# tiny_encoder_board.net
KiCad netlist of a schematic drawn in EAGLE
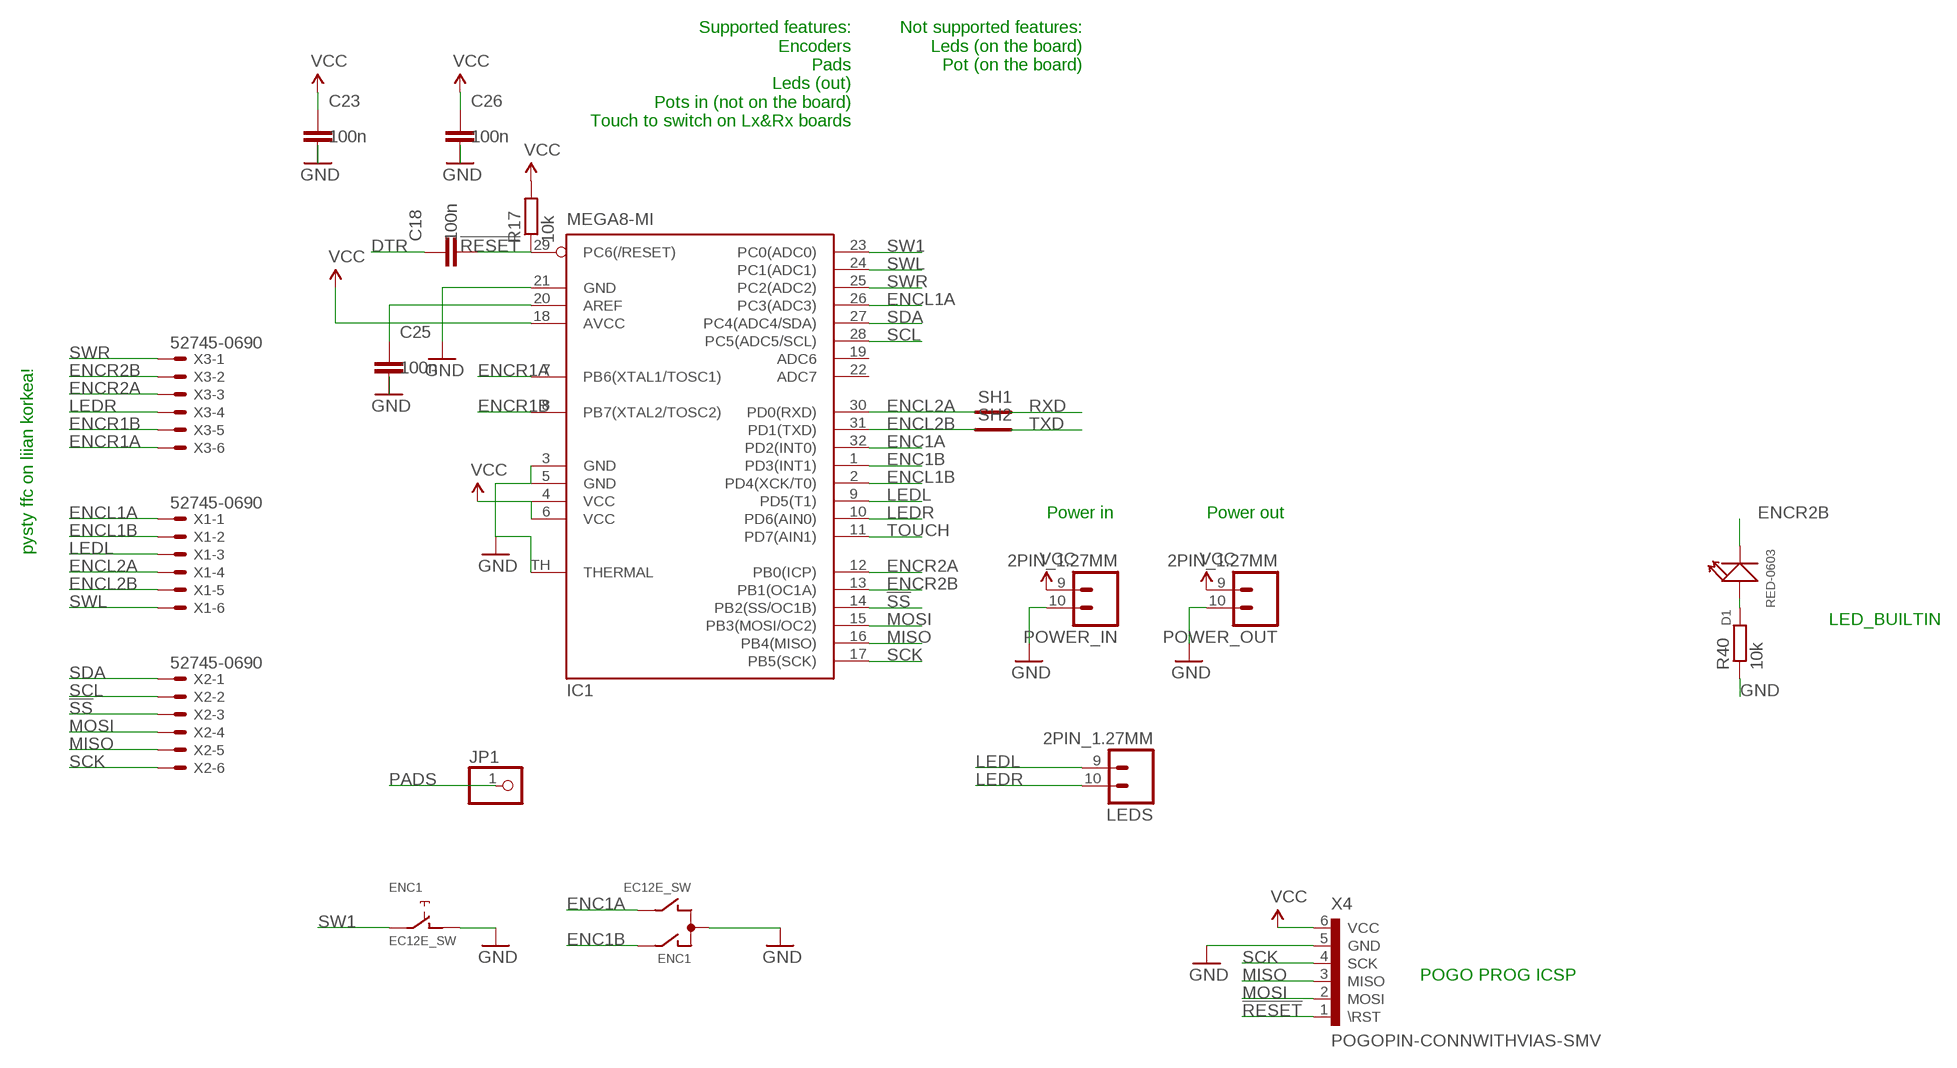
[diagram p0: schematic, sheet 1]
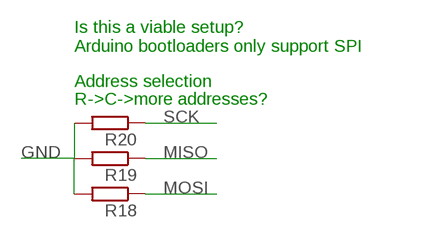
[diagram p1: schematic, sheet 2]
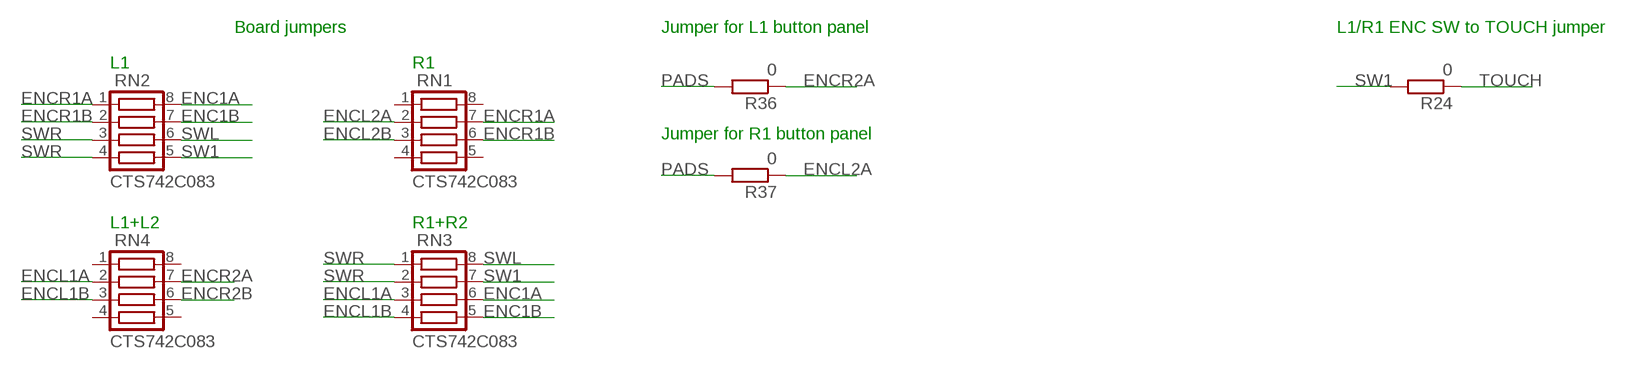
[diagram p2: schematic, sheet 3]

(export (version "E")
  (design (tool "Eeschema 10.0.6"))
  (components
    (comp (ref "C18")
      (value "100n")
      (footprint "eagle-import:C0402")
      (libsource (lib "eagle-import") (part "C-EUC0402"))
    )
    (comp (ref "C23")
      (value "100n")
      (footprint "eagle-import:C0402")
      (libsource (lib "eagle-import") (part "C-EUC0402"))
    )
    (comp (ref "C25")
      (value "100n")
      (footprint "eagle-import:C0402")
      (libsource (lib "eagle-import") (part "C-EUC0402"))
    )
    (comp (ref "C26")
      (value "100n")
      (footprint "eagle-import:C0402")
      (libsource (lib "eagle-import") (part "C-EUC0402"))
    )
    (comp (ref "D1")
      (value "RED-0603")
      (footprint "eagle-import:LED-0603")
      (fields (field (name "MPN") "19-217-R6C-AL1M2VY-3T"))
      (libsource (lib "eagle-import") (part "LED-SMD-RED-DIFFUSED(0603)"))
    )
    (comp (ref "ENC1")
      (value "EC12E_SW")
      (footprint "eagle-import:ALPS_EC12E_SW")
      (fields (field (name "MPN") "EC12E2424407"))
      (libsource (lib "eagle-import") (part "EC12E_SW"))
    )
    (comp (ref "IC1")
      (value "MEGA8-MI")
      (footprint "eagle-import:MLF32-TH")
      (fields (field (name "MPN") "ATMEGA88PA-MU"))
      (libsource (lib "eagle-import") (part "MEGA8-MI"))
    )
    (comp (ref "JP1")
      (value "PINHD-1X1")
      (footprint "eagle-import:1X01")
      (libsource (lib "eagle-import") (part "PINHD-1X1"))
    )
    (comp (ref "LEDS")
      (value "2PIN_1.27MM")
      (footprint "eagle-import:1X02_1.27MM_NO_SILK")
      (libsource (lib "eagle-import") (part "2PIN_1.27MM"))
    )
    (comp (ref "POWER_IN")
      (value "2PIN_1.27MM")
      (footprint "eagle-import:1X02_1.27MM_NO_SILK")
      (libsource (lib "eagle-import") (part "2PIN_1.27MM"))
    )
    (comp (ref "POWER_OUT")
      (value "2PIN_1.27MM")
      (footprint "eagle-import:1X02_1.27MM_NO_SILK")
      (libsource (lib "eagle-import") (part "2PIN_1.27MM"))
    )
    (comp (ref "R17")
      (value "10k")
      (footprint "eagle-import:R0402")
      (libsource (lib "eagle-import") (part "rcl_334_R-EU_R0402"))
    )
    (comp (ref "R40")
      (value "10k")
      (footprint "eagle-import:R0402")
      (libsource (lib "eagle-import") (part "rcl_334_R-EU_R0402"))
    )
    (comp (ref "SH1")
      (value "SHORT")
      (footprint "eagle-import:SHORT_TOP_8MIL")
      (libsource (lib "eagle-import") (part "SHORT"))
    )
    (comp (ref "SH2")
      (value "SHORT")
      (footprint "eagle-import:SHORT_TOP_8MIL")
      (libsource (lib "eagle-import") (part "SHORT"))
    )
    (comp (ref "X1")
      (value "52745-0690")
      (footprint "eagle-import:52745-0690")
      (fields (field (name "MF") "MOLEX"))
      (libsource (lib "eagle-import") (part "52745-0690"))
    )
    (comp (ref "X2")
      (value "52745-0690")
      (footprint "eagle-import:52745-0690")
      (fields (field (name "MF") "MOLEX"))
      (libsource (lib "eagle-import") (part "52745-0690"))
    )
    (comp (ref "X3")
      (value "52745-0690")
      (footprint "eagle-import:52745-0690")
      (fields (field (name "MF") "MOLEX"))
      (libsource (lib "eagle-import") (part "52745-0690"))
    )
    (comp (ref "X4")
      (value "POGOPIN-CONNWITHVIAS-SMV")
      (footprint "eagle-import:POGOPROG-CONN-OH-SMALLERVIAS")
      (libsource (lib "eagle-import") (part "POGOPIN-CONNWITHVIAS-SMV"))
    )
    (comp (ref "R24")
      (value "0")
      (footprint "eagle-import:R0402")
      (fields (field (name "SPICEPREFIX") "R"))
      (libsource (lib "eagle-import") (part "rcl_334_R-EU_R0402"))
    )
    (comp (ref "R36")
      (value "0")
      (footprint "eagle-import:R0603")
      (fields (field (name "SPICEPREFIX") "R"))
      (libsource (lib "eagle-import") (part "R-EU_R0603"))
    )
    (comp (ref "R37")
      (value "0")
      (footprint "eagle-import:R0402")
      (fields (field (name "SPICEPREFIX") "R"))
      (libsource (lib "eagle-import") (part "rcl_334_R-EU_R0402"))
    )
    (comp (ref "RN1")
      (value "CTS742C083")
      (footprint "eagle-import:CTS742C083")
      (libsource (lib "eagle-import") (part "CTS742C083"))
    )
    (comp (ref "RN2")
      (value "CTS742C083")
      (footprint "eagle-import:CTS742C083")
      (libsource (lib "eagle-import") (part "CTS742C083"))
    )
    (comp (ref "RN3")
      (value "CTS742C083")
      (footprint "eagle-import:CTS742C083")
      (libsource (lib "eagle-import") (part "CTS742C083"))
    )
    (comp (ref "RN4")
      (value "CTS742C083")
      (footprint "eagle-import:CTS742C083")
      (libsource (lib "eagle-import") (part "CTS742C083"))
    )
    (comp (ref "R18")
      (value "R-EU_R0402")
      (footprint "eagle-import:R0402")
      (libsource (lib "eagle-import") (part "rcl_334_R-EU_R0402"))
    )
    (comp (ref "R19")
      (value "R-EU_R0402")
      (footprint "eagle-import:R0402")
      (libsource (lib "eagle-import") (part "rcl_334_R-EU_R0402"))
    )
    (comp (ref "R20")
      (value "R-EU_R0402")
      (footprint "eagle-import:R0402")
      (libsource (lib "eagle-import") (part "rcl_334_R-EU_R0402"))
    )
  )
  (nets
    (net (code "1") (name "DTR") (class "Default")
      (node (ref "C18") (pin "1") (pinfunction "1_1") (pintype "passive"))
    )
    (net (code "2") (name "ENC1A") (class "Default")
      (node (ref "ENC1") (pin "B") (pinfunction "B_B") (pintype "passive"))
      (node (ref "IC1") (pin "32") (pinfunction "PD2(INT0)_32") (pintype "bidirectional"))
      (node (ref "RN2") (pin "8") (pinfunction "8_8") (pintype "passive"))
      (node (ref "RN3") (pin "6") (pinfunction "6_6") (pintype "passive"))
    )
    (net (code "3") (name "ENC1B") (class "Default")
      (node (ref "ENC1") (pin "A") (pinfunction "A_A") (pintype "passive"))
      (node (ref "IC1") (pin "1") (pinfunction "PD3(INT1)_1") (pintype "bidirectional"))
      (node (ref "RN2") (pin "7") (pinfunction "7_7") (pintype "passive"))
      (node (ref "RN3") (pin "5") (pinfunction "5_5") (pintype "passive"))
    )
    (net (code "4") (name "ENCL1A") (class "Default")
      (node (ref "IC1") (pin "26") (pinfunction "PC3(ADC3)_26") (pintype "bidirectional"))
      (node (ref "RN3") (pin "3") (pinfunction "3_3") (pintype "passive"))
      (node (ref "RN4") (pin "2") (pinfunction "2_2") (pintype "passive"))
      (node (ref "X1") (pin "1") (pinfunction "S_1") (pintype "passive"))
    )
    (net (code "5") (name "ENCL1B") (class "Default")
      (node (ref "IC1") (pin "2") (pinfunction "PD4(XCK/T0)_2") (pintype "bidirectional"))
      (node (ref "RN3") (pin "4") (pinfunction "4_4") (pintype "passive"))
      (node (ref "RN4") (pin "3") (pinfunction "3_3") (pintype "passive"))
      (node (ref "X1") (pin "2") (pinfunction "S_2") (pintype "passive"))
    )
    (net (code "6") (name "ENCL2A") (class "Default")
      (node (ref "IC1") (pin "30") (pinfunction "PD0(RXD)_30") (pintype "bidirectional"))
      (node (ref "R37") (pin "1") (pinfunction "1_1") (pintype "passive"))
      (node (ref "RN1") (pin "2") (pinfunction "2_2") (pintype "passive"))
      (node (ref "SH1") (pin "P$1") (pinfunction "P$1_P$1") (pintype "bidirectional"))
      (node (ref "X1") (pin "4") (pinfunction "S_4") (pintype "passive"))
    )
    (net (code "7") (name "ENCL2B") (class "Default")
      (node (ref "IC1") (pin "31") (pinfunction "PD1(TXD)_31") (pintype "bidirectional"))
      (node (ref "RN1") (pin "3") (pinfunction "3_3") (pintype "passive"))
      (node (ref "SH2") (pin "P$1") (pinfunction "P$1_P$1") (pintype "bidirectional"))
      (node (ref "X1") (pin "5") (pinfunction "S_5") (pintype "passive"))
    )
    (net (code "8") (name "ENCR1A") (class "Default")
      (node (ref "IC1") (pin "7") (pinfunction "PB6(XTAL1/TOSC1)_7") (pintype "bidirectional"))
      (node (ref "RN1") (pin "7") (pinfunction "7_7") (pintype "passive"))
      (node (ref "RN2") (pin "1") (pinfunction "1_1") (pintype "passive"))
      (node (ref "X3") (pin "6") (pinfunction "S_6") (pintype "passive"))
    )
    (net (code "9") (name "ENCR1B") (class "Default")
      (node (ref "IC1") (pin "8") (pinfunction "PB7(XTAL2/TOSC2)_8") (pintype "bidirectional"))
      (node (ref "RN1") (pin "6") (pinfunction "6_6") (pintype "passive"))
      (node (ref "RN2") (pin "2") (pinfunction "2_2") (pintype "passive"))
      (node (ref "X3") (pin "5") (pinfunction "S_5") (pintype "passive"))
    )
    (net (code "10") (name "ENCR2A") (class "Default")
      (node (ref "IC1") (pin "12") (pinfunction "PB0(ICP)_12") (pintype "bidirectional"))
      (node (ref "R36") (pin "1") (pinfunction "1_1") (pintype "passive"))
      (node (ref "RN4") (pin "7") (pinfunction "7_7") (pintype "passive"))
      (node (ref "X3") (pin "3") (pinfunction "S_3") (pintype "passive"))
    )
    (net (code "11") (name "ENCR2B") (class "Default")
      (node (ref "D1") (pin "-") (pinfunction "-_-") (pintype "passive"))
      (node (ref "IC1") (pin "13") (pinfunction "PB1(OC1A)_13") (pintype "bidirectional"))
      (node (ref "RN4") (pin "6") (pinfunction "6_6") (pintype "passive"))
      (node (ref "X3") (pin "2") (pinfunction "S_2") (pintype "passive"))
    )
    (net (code "12") (name "GND") (class "Default")
      (node (ref "C23") (pin "2") (pinfunction "2_2") (pintype "passive"))
      (node (ref "C25") (pin "2") (pinfunction "2_2") (pintype "passive"))
      (node (ref "C26") (pin "2") (pinfunction "2_2") (pintype "passive"))
      (node (ref "ENC1") (pin "C") (pinfunction "C_C") (pintype "passive"))
      (node (ref "ENC1") (pin "D") (pinfunction "1_D") (pintype "passive"))
      (node (ref "IC1") (pin "21") (pinfunction "GND_21") (pintype "power_in"))
      (node (ref "IC1") (pin "3") (pinfunction "GND_3") (pintype "power_in"))
      (node (ref "IC1") (pin "5") (pinfunction "GND_5") (pintype "power_in"))
      (node (ref "IC1") (pin "TH") (pinfunction "THERMAL_TH") (pintype "passive"))
      (node (ref "POWER_IN") (pin "10") (pinfunction "2_10") (pintype "passive"))
      (node (ref "POWER_OUT") (pin "10") (pinfunction "2_10") (pintype "passive"))
      (node (ref "R18") (pin "2") (pinfunction "2_2") (pintype "passive"))
      (node (ref "R19") (pin "2") (pinfunction "2_2") (pintype "passive"))
      (node (ref "R20") (pin "2") (pinfunction "2_2") (pintype "passive"))
      (node (ref "R40") (pin "1") (pinfunction "1_1") (pintype "passive"))
      (node (ref "X4") (pin "5") (pinfunction "GND_5") (pintype "bidirectional"))
    )
    (net (code "13") (name "LEDL") (class "Default")
      (node (ref "IC1") (pin "9") (pinfunction "PD5(T1)_9") (pintype "bidirectional"))
      (node (ref "LEDS") (pin "9") (pinfunction "1_9") (pintype "passive"))
      (node (ref "X1") (pin "3") (pinfunction "S_3") (pintype "passive"))
    )
    (net (code "14") (name "LEDR") (class "Default")
      (node (ref "IC1") (pin "10") (pinfunction "PD6(AIN0)_10") (pintype "bidirectional"))
      (node (ref "LEDS") (pin "10") (pinfunction "2_10") (pintype "passive"))
      (node (ref "X3") (pin "4") (pinfunction "S_4") (pintype "passive"))
    )
    (net (code "15") (name "MISO") (class "Default")
      (node (ref "IC1") (pin "16") (pinfunction "PB4(MISO)_16") (pintype "bidirectional"))
      (node (ref "R19") (pin "1") (pinfunction "1_1") (pintype "passive"))
      (node (ref "X2") (pin "5") (pinfunction "S_5") (pintype "passive"))
      (node (ref "X4") (pin "3") (pinfunction "MISO_3") (pintype "bidirectional"))
    )
    (net (code "16") (name "MOSI") (class "Default")
      (node (ref "IC1") (pin "15") (pinfunction "PB3(MOSI/OC2)_15") (pintype "bidirectional"))
      (node (ref "R18") (pin "1") (pinfunction "1_1") (pintype "passive"))
      (node (ref "X2") (pin "4") (pinfunction "S_4") (pintype "passive"))
      (node (ref "X4") (pin "2") (pinfunction "MOSI_2") (pintype "bidirectional"))
    )
    (net (code "17") (name "Net-(D1-Pad+)") (class "Default")
      (node (ref "D1") (pin "+") (pinfunction "+_+") (pintype "passive"))
      (node (ref "R40") (pin "2") (pinfunction "2_2") (pintype "passive"))
    )
    (net (code "18") (name "Net-(IC1-AREF)") (class "Default")
      (node (ref "C25") (pin "1") (pinfunction "1_1") (pintype "passive"))
      (node (ref "IC1") (pin "20") (pinfunction "AREF_20") (pintype "passive"))
    )
    (net (code "19") (name "PADS") (class "Default")
      (node (ref "JP1") (pin "1") (pinfunction "1_1") (pintype "passive"))
      (node (ref "R36") (pin "2") (pinfunction "2_2") (pintype "passive"))
      (node (ref "R37") (pin "2") (pinfunction "2_2") (pintype "passive"))
    )
    (net (code "20") (name "RXD") (class "Default")
      (node (ref "SH1") (pin "P$2") (pinfunction "P$2_P$2") (pintype "bidirectional"))
    )
    (net (code "21") (name "SCK") (class "Default")
      (node (ref "IC1") (pin "17") (pinfunction "PB5(SCK)_17") (pintype "bidirectional"))
      (node (ref "R20") (pin "1") (pinfunction "1_1") (pintype "passive"))
      (node (ref "X2") (pin "6") (pinfunction "S_6") (pintype "passive"))
      (node (ref "X4") (pin "4") (pinfunction "SCK_4") (pintype "bidirectional"))
    )
    (net (code "22") (name "SCL") (class "Default")
      (node (ref "IC1") (pin "28") (pinfunction "PC5(ADC5/SCL)_28") (pintype "bidirectional"))
      (node (ref "X2") (pin "2") (pinfunction "S_2") (pintype "passive"))
    )
    (net (code "23") (name "SDA") (class "Default")
      (node (ref "IC1") (pin "27") (pinfunction "PC4(ADC4/SDA)_27") (pintype "bidirectional"))
      (node (ref "X2") (pin "1") (pinfunction "S_1") (pintype "passive"))
    )
    (net (code "24") (name "SW1") (class "Default")
      (node (ref "ENC1") (pin "E") (pinfunction "2_E") (pintype "passive"))
      (node (ref "IC1") (pin "23") (pinfunction "PC0(ADC0)_23") (pintype "bidirectional"))
      (node (ref "R24") (pin "2") (pinfunction "2_2") (pintype "passive"))
      (node (ref "RN2") (pin "5") (pinfunction "5_5") (pintype "passive"))
      (node (ref "RN3") (pin "7") (pinfunction "7_7") (pintype "passive"))
    )
    (net (code "25") (name "SWL") (class "Default")
      (node (ref "IC1") (pin "24") (pinfunction "PC1(ADC1)_24") (pintype "bidirectional"))
      (node (ref "RN2") (pin "6") (pinfunction "6_6") (pintype "passive"))
      (node (ref "RN3") (pin "8") (pinfunction "8_8") (pintype "passive"))
      (node (ref "X1") (pin "6") (pinfunction "S_6") (pintype "passive"))
    )
    (net (code "26") (name "SWR") (class "Default")
      (node (ref "IC1") (pin "25") (pinfunction "PC2(ADC2)_25") (pintype "bidirectional"))
      (node (ref "RN2") (pin "3") (pinfunction "3_3") (pintype "passive"))
      (node (ref "RN2") (pin "4") (pinfunction "4_4") (pintype "passive"))
      (node (ref "RN3") (pin "1") (pinfunction "1_1") (pintype "passive"))
      (node (ref "RN3") (pin "2") (pinfunction "2_2") (pintype "passive"))
      (node (ref "X3") (pin "1") (pinfunction "S_1") (pintype "passive"))
    )
    (net (code "27") (name "TOUCH") (class "Default")
      (node (ref "IC1") (pin "11") (pinfunction "PD7(AIN1)_11") (pintype "bidirectional"))
      (node (ref "R24") (pin "1") (pinfunction "1_1") (pintype "passive"))
    )
    (net (code "28") (name "TXD") (class "Default")
      (node (ref "SH2") (pin "P$2") (pinfunction "P$2_P$2") (pintype "bidirectional"))
    )
    (net (code "29") (name "VCC") (class "Default")
      (node (ref "C23") (pin "1") (pinfunction "1_1") (pintype "passive"))
      (node (ref "C26") (pin "1") (pinfunction "1_1") (pintype "passive"))
      (node (ref "IC1") (pin "18") (pinfunction "AVCC_18") (pintype "power_in"))
      (node (ref "IC1") (pin "4") (pinfunction "VCC_4") (pintype "power_in"))
      (node (ref "IC1") (pin "6") (pinfunction "VCC_6") (pintype "power_in"))
      (node (ref "POWER_IN") (pin "9") (pinfunction "1_9") (pintype "passive"))
      (node (ref "POWER_OUT") (pin "9") (pinfunction "1_9") (pintype "passive"))
      (node (ref "R17") (pin "2") (pinfunction "2_2") (pintype "passive"))
      (node (ref "X4") (pin "6") (pinfunction "VCC_6") (pintype "bidirectional"))
    )
    (net (code "30") (name "unconnected-(IC1-ADC6-Pad19)") (class "Default")
      (node (ref "IC1") (pin "19") (pinfunction "ADC6_19") (pintype "bidirectional"))
    )
    (net (code "31") (name "unconnected-(IC1-ADC7-Pad22)") (class "Default")
      (node (ref "IC1") (pin "22") (pinfunction "ADC7_22") (pintype "bidirectional"))
    )
    (net (code "32") (name "unconnected-(RN1-Pad1)") (class "Default")
      (node (ref "RN1") (pin "1") (pinfunction "1_1") (pintype "passive"))
    )
    (net (code "33") (name "unconnected-(RN1-Pad4)") (class "Default")
      (node (ref "RN1") (pin "4") (pinfunction "4_4") (pintype "passive"))
    )
    (net (code "34") (name "unconnected-(RN1-Pad5)") (class "Default")
      (node (ref "RN1") (pin "5") (pinfunction "5_5") (pintype "passive"))
    )
    (net (code "35") (name "unconnected-(RN1-Pad8)") (class "Default")
      (node (ref "RN1") (pin "8") (pinfunction "8_8") (pintype "passive"))
    )
    (net (code "36") (name "unconnected-(RN4-Pad1)") (class "Default")
      (node (ref "RN4") (pin "1") (pinfunction "1_1") (pintype "passive"))
    )
    (net (code "37") (name "unconnected-(RN4-Pad4)") (class "Default")
      (node (ref "RN4") (pin "4") (pinfunction "4_4") (pintype "passive"))
    )
    (net (code "38") (name "unconnected-(RN4-Pad5)") (class "Default")
      (node (ref "RN4") (pin "5") (pinfunction "5_5") (pintype "passive"))
    )
    (net (code "39") (name "unconnected-(RN4-Pad8)") (class "Default")
      (node (ref "RN4") (pin "8") (pinfunction "8_8") (pintype "passive"))
    )
    (net (code "40") (name "~{RESET}") (class "Default")
      (node (ref "C18") (pin "2") (pinfunction "2_2") (pintype "passive"))
      (node (ref "IC1") (pin "29") (pinfunction "PC6(/RESET)_29") (pintype "bidirectional"))
      (node (ref "R17") (pin "1") (pinfunction "1_1") (pintype "passive"))
      (node (ref "X4") (pin "1") (pinfunction "\\RST_1") (pintype "bidirectional"))
    )
    (net (code "41") (name "~{SS}") (class "Default")
      (node (ref "IC1") (pin "14") (pinfunction "PB2(SS/OC1B)_14") (pintype "bidirectional"))
      (node (ref "X2") (pin "3") (pinfunction "S_3") (pintype "passive"))
    )
  )
)
